# isolation.net
KiCad netlist of a schematic drawn in Altium Designer
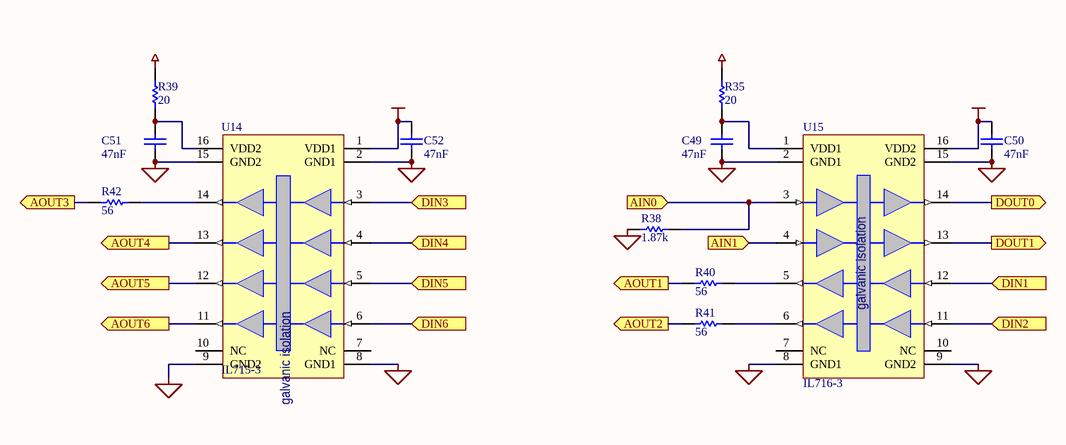
[diagram p0: isolation.SCHDOC]

(export (version "E")
  (design (tool "Eeschema 10.0.6"))
  (components
    (comp (ref "C49")
      (value "47nF")
      (footprint "CC1608-0603")
      (description "Capacitor")
      (fields
        (field (name "MANUFACTURER") "Generic Components")
        (field (name "Comment") "Cap")
        (field (name "PUBLISHER") "Altium Limited")
      )
      (libsource (lib "Miscellaneous Devices") (part "Cap"))
    )
    (comp (ref "C50")
      (value "47nF")
      (footprint "CC1608-0603")
      (description "Capacitor")
      (fields
        (field (name "MANUFACTURER") "Generic Components")
        (field (name "Comment") "Cap")
        (field (name "PUBLISHER") "Altium Limited")
      )
      (libsource (lib "Miscellaneous Devices") (part "Cap"))
    )
    (comp (ref "C51")
      (value "47nF")
      (footprint "CC1608-0603")
      (description "Capacitor")
      (fields
        (field (name "MANUFACTURER") "Generic Components")
        (field (name "Comment") "Cap")
        (field (name "PUBLISHER") "Altium Limited")
      )
      (libsource (lib "Miscellaneous Devices") (part "Cap"))
    )
    (comp (ref "C52")
      (value "47nF")
      (footprint "CC1608-0603")
      (description "Capacitor")
      (fields
        (field (name "MANUFACTURER") "Generic Components")
        (field (name "Comment") "Cap")
        (field (name "PUBLISHER") "Altium Limited")
      )
      (libsource (lib "Miscellaneous Devices") (part "Cap"))
    )
    (comp (ref "R35")
      (value "20")
      (footprint "CC1608-0603")
      (description "Resistor")
      (fields
        (field (name "MANUFACTURER") "Generic Components")
        (field (name "Comment") "Res1")
        (field (name "PUBLISHER") "Altium Limited")
      )
      (libsource (lib "Miscellaneous Devices") (part "Res1"))
    )
    (comp (ref "R38")
      (value "1.87k")
      (footprint "CC1608-0603")
      (description "Resistor")
      (fields
        (field (name "MANUFACTURER") "Generic Components")
        (field (name "Comment") "Res1")
        (field (name "PUBLISHER") "Altium Limited")
      )
      (libsource (lib "Miscellaneous Devices") (part "Res1"))
    )
    (comp (ref "R39")
      (value "20")
      (footprint "CC1608-0603")
      (description "Resistor")
      (fields
        (field (name "MANUFACTURER") "Generic Components")
        (field (name "Comment") "Res1")
        (field (name "PUBLISHER") "Altium Limited")
      )
      (libsource (lib "Miscellaneous Devices") (part "Res1"))
    )
    (comp (ref "R40")
      (value "56")
      (footprint "CC1608-0603")
      (description "Resistor")
      (fields
        (field (name "MANUFACTURER") "Generic Components")
        (field (name "Comment") "Res1")
        (field (name "PUBLISHER") "Altium Limited")
      )
      (libsource (lib "Miscellaneous Devices") (part "Res1"))
    )
    (comp (ref "R41")
      (value "56")
      (footprint "CC1608-0603")
      (description "Resistor")
      (fields
        (field (name "MANUFACTURER") "Generic Components")
        (field (name "Comment") "Res1")
        (field (name "PUBLISHER") "Altium Limited")
      )
      (libsource (lib "Miscellaneous Devices") (part "Res1"))
    )
    (comp (ref "R42")
      (value "56")
      (footprint "CC1608-0603")
      (description "Resistor")
      (fields
        (field (name "MANUFACTURER") "Generic Components")
        (field (name "Comment") "Res1")
        (field (name "PUBLISHER") "Altium Limited")
      )
      (libsource (lib "Miscellaneous Devices") (part "Res1"))
    )
    (comp (ref "U14")
      (value "IL715-3")
      (footprint "SO-G16/D10")
      (description "High speed digital coupler")
      (libsource (lib "parts") (part "IL715-3"))
    )
    (comp (ref "U15")
      (value "IL716-3")
      (footprint "SO-G16/D10")
      (description "High speed digital coupler")
      (libsource (lib "parts") (part "IL716-3"))
    )
  )
  (nets
    (net (code "1") (name "/AIN0") (class "Default")
      (node (ref "R38") (pin "2") (pinfunction "2_2") (pintype "passive"))
      (node (ref "U15") (pin "3") (pinfunction "IN1_3") (pintype "input"))
    )
    (net (code "2") (name "/AIN1") (class "Default")
      (node (ref "U15") (pin "4") (pinfunction "IN2_4") (pintype "input"))
    )
    (net (code "3") (name "/AOUT1") (class "Default")
      (node (ref "R40") (pin "1") (pinfunction "1_1") (pintype "passive"))
    )
    (net (code "4") (name "/AOUT2") (class "Default")
      (node (ref "R41") (pin "1") (pinfunction "1_1") (pintype "passive"))
    )
    (net (code "5") (name "/AOUT3") (class "Default")
      (node (ref "R42") (pin "1") (pinfunction "1_1") (pintype "passive"))
    )
    (net (code "6") (name "/AOUT4") (class "Default")
      (node (ref "U14") (pin "13") (pinfunction "OUT2_13") (pintype "output"))
    )
    (net (code "7") (name "/AOUT5") (class "Default")
      (node (ref "U14") (pin "12") (pinfunction "OUT3_12") (pintype "output"))
    )
    (net (code "8") (name "/AOUT6") (class "Default")
      (node (ref "U14") (pin "11") (pinfunction "OUT4_11") (pintype "output"))
    )
    (net (code "9") (name "/DIN1") (class "Default")
      (node (ref "U15") (pin "12") (pinfunction "IN3_12") (pintype "input"))
    )
    (net (code "10") (name "/DIN2") (class "Default")
      (node (ref "U15") (pin "11") (pinfunction "IN4_11") (pintype "input"))
    )
    (net (code "11") (name "/DIN3") (class "Default")
      (node (ref "U14") (pin "3") (pinfunction "IN1_3") (pintype "input"))
    )
    (net (code "12") (name "/DIN4") (class "Default")
      (node (ref "U14") (pin "4") (pinfunction "IN2_4") (pintype "input"))
    )
    (net (code "13") (name "/DIN5") (class "Default")
      (node (ref "U14") (pin "5") (pinfunction "IN3_5") (pintype "input"))
    )
    (net (code "14") (name "/DIN6") (class "Default")
      (node (ref "U14") (pin "6") (pinfunction "IN4_6") (pintype "input"))
    )
    (net (code "15") (name "/DOUT0") (class "Default")
      (node (ref "U15") (pin "14") (pinfunction "OUT1_14") (pintype "output"))
    )
    (net (code "16") (name "/DOUT1") (class "Default")
      (node (ref "U15") (pin "13") (pinfunction "OUT2_13") (pintype "output"))
    )
    (net (code "17") (name "AGND") (class "Default")
      (node (ref "C49") (pin "1") (pinfunction "1_1") (pintype "passive"))
      (node (ref "C51") (pin "1") (pinfunction "1_1") (pintype "passive"))
      (node (ref "R38") (pin "1") (pinfunction "1_1") (pintype "passive"))
      (node (ref "U14") (pin "15") (pinfunction "GND2_15") (pintype "power_in"))
      (node (ref "U14") (pin "9") (pinfunction "GND2_9") (pintype "power_in"))
      (node (ref "U15") (pin "2") (pinfunction "GND1_2") (pintype "power_in"))
      (node (ref "U15") (pin "8") (pinfunction "GND1_8") (pintype "power_in"))
    )
    (net (code "18") (name "AVDD") (class "Default")
      (node (ref "R35") (pin "2") (pinfunction "2_2") (pintype "passive"))
      (node (ref "R39") (pin "2") (pinfunction "2_2") (pintype "passive"))
    )
    (net (code "19") (name "GND") (class "Default")
      (node (ref "C50") (pin "1") (pinfunction "1_1") (pintype "passive"))
      (node (ref "C52") (pin "1") (pinfunction "1_1") (pintype "passive"))
      (node (ref "U14") (pin "2") (pinfunction "GND1_2") (pintype "power_in"))
      (node (ref "U14") (pin "8") (pinfunction "GND1_8") (pintype "power_in"))
      (node (ref "U15") (pin "15") (pinfunction "GND2_15") (pintype "power_in"))
      (node (ref "U15") (pin "9") (pinfunction "GND2_9") (pintype "power_in"))
    )
    (net (code "20") (name "Net-(U14-OUT1)") (class "Default")
      (node (ref "R42") (pin "2") (pinfunction "2_2") (pintype "passive"))
      (node (ref "U14") (pin "14") (pinfunction "OUT1_14") (pintype "output"))
    )
    (net (code "21") (name "Net-(U14-VDD2)") (class "Default")
      (node (ref "C51") (pin "2") (pinfunction "2_2") (pintype "passive"))
      (node (ref "R39") (pin "1") (pinfunction "1_1") (pintype "passive"))
      (node (ref "U14") (pin "16") (pinfunction "VDD2_16") (pintype "power_in"))
    )
    (net (code "22") (name "Net-(U15-OUT3)") (class "Default")
      (node (ref "R40") (pin "2") (pinfunction "2_2") (pintype "passive"))
      (node (ref "U15") (pin "5") (pinfunction "OUT3_5") (pintype "output"))
    )
    (net (code "23") (name "Net-(U15-OUT4)") (class "Default")
      (node (ref "R41") (pin "2") (pinfunction "2_2") (pintype "passive"))
      (node (ref "U15") (pin "6") (pinfunction "OUT4_6") (pintype "output"))
    )
    (net (code "24") (name "Net-(U15-VDD1)") (class "Default")
      (node (ref "C49") (pin "2") (pinfunction "2_2") (pintype "passive"))
      (node (ref "R35") (pin "1") (pinfunction "1_1") (pintype "passive"))
      (node (ref "U15") (pin "1") (pinfunction "VDD1_1") (pintype "power_in"))
    )
    (net (code "25") (name "VCC") (class "Default")
      (node (ref "C50") (pin "2") (pinfunction "2_2") (pintype "passive"))
      (node (ref "C52") (pin "2") (pinfunction "2_2") (pintype "passive"))
      (node (ref "U14") (pin "1") (pinfunction "VDD1_1") (pintype "power_in"))
      (node (ref "U15") (pin "16") (pinfunction "VDD2_16") (pintype "power_in"))
    )
    (net (code "26") (name "unconnected-(U14-NC-Pad7)") (class "Default")
      (node (ref "U14") (pin "7") (pinfunction "NC_7") (pintype "passive"))
    )
    (net (code "27") (name "unconnected-(U14-NC-Pad10)") (class "Default")
      (node (ref "U14") (pin "10") (pinfunction "NC_10") (pintype "passive"))
    )
    (net (code "28") (name "unconnected-(U15-NC-Pad7)") (class "Default")
      (node (ref "U15") (pin "7") (pinfunction "NC_7") (pintype "passive"))
    )
    (net (code "29") (name "unconnected-(U15-NC-Pad10)") (class "Default")
      (node (ref "U15") (pin "10") (pinfunction "NC_10") (pintype "passive"))
    )
  )
)
